# Cosmic_Pi_Main_Board_V2_5_OHL_no_logo.net
KiCad netlist of a schematic drawn in EAGLE
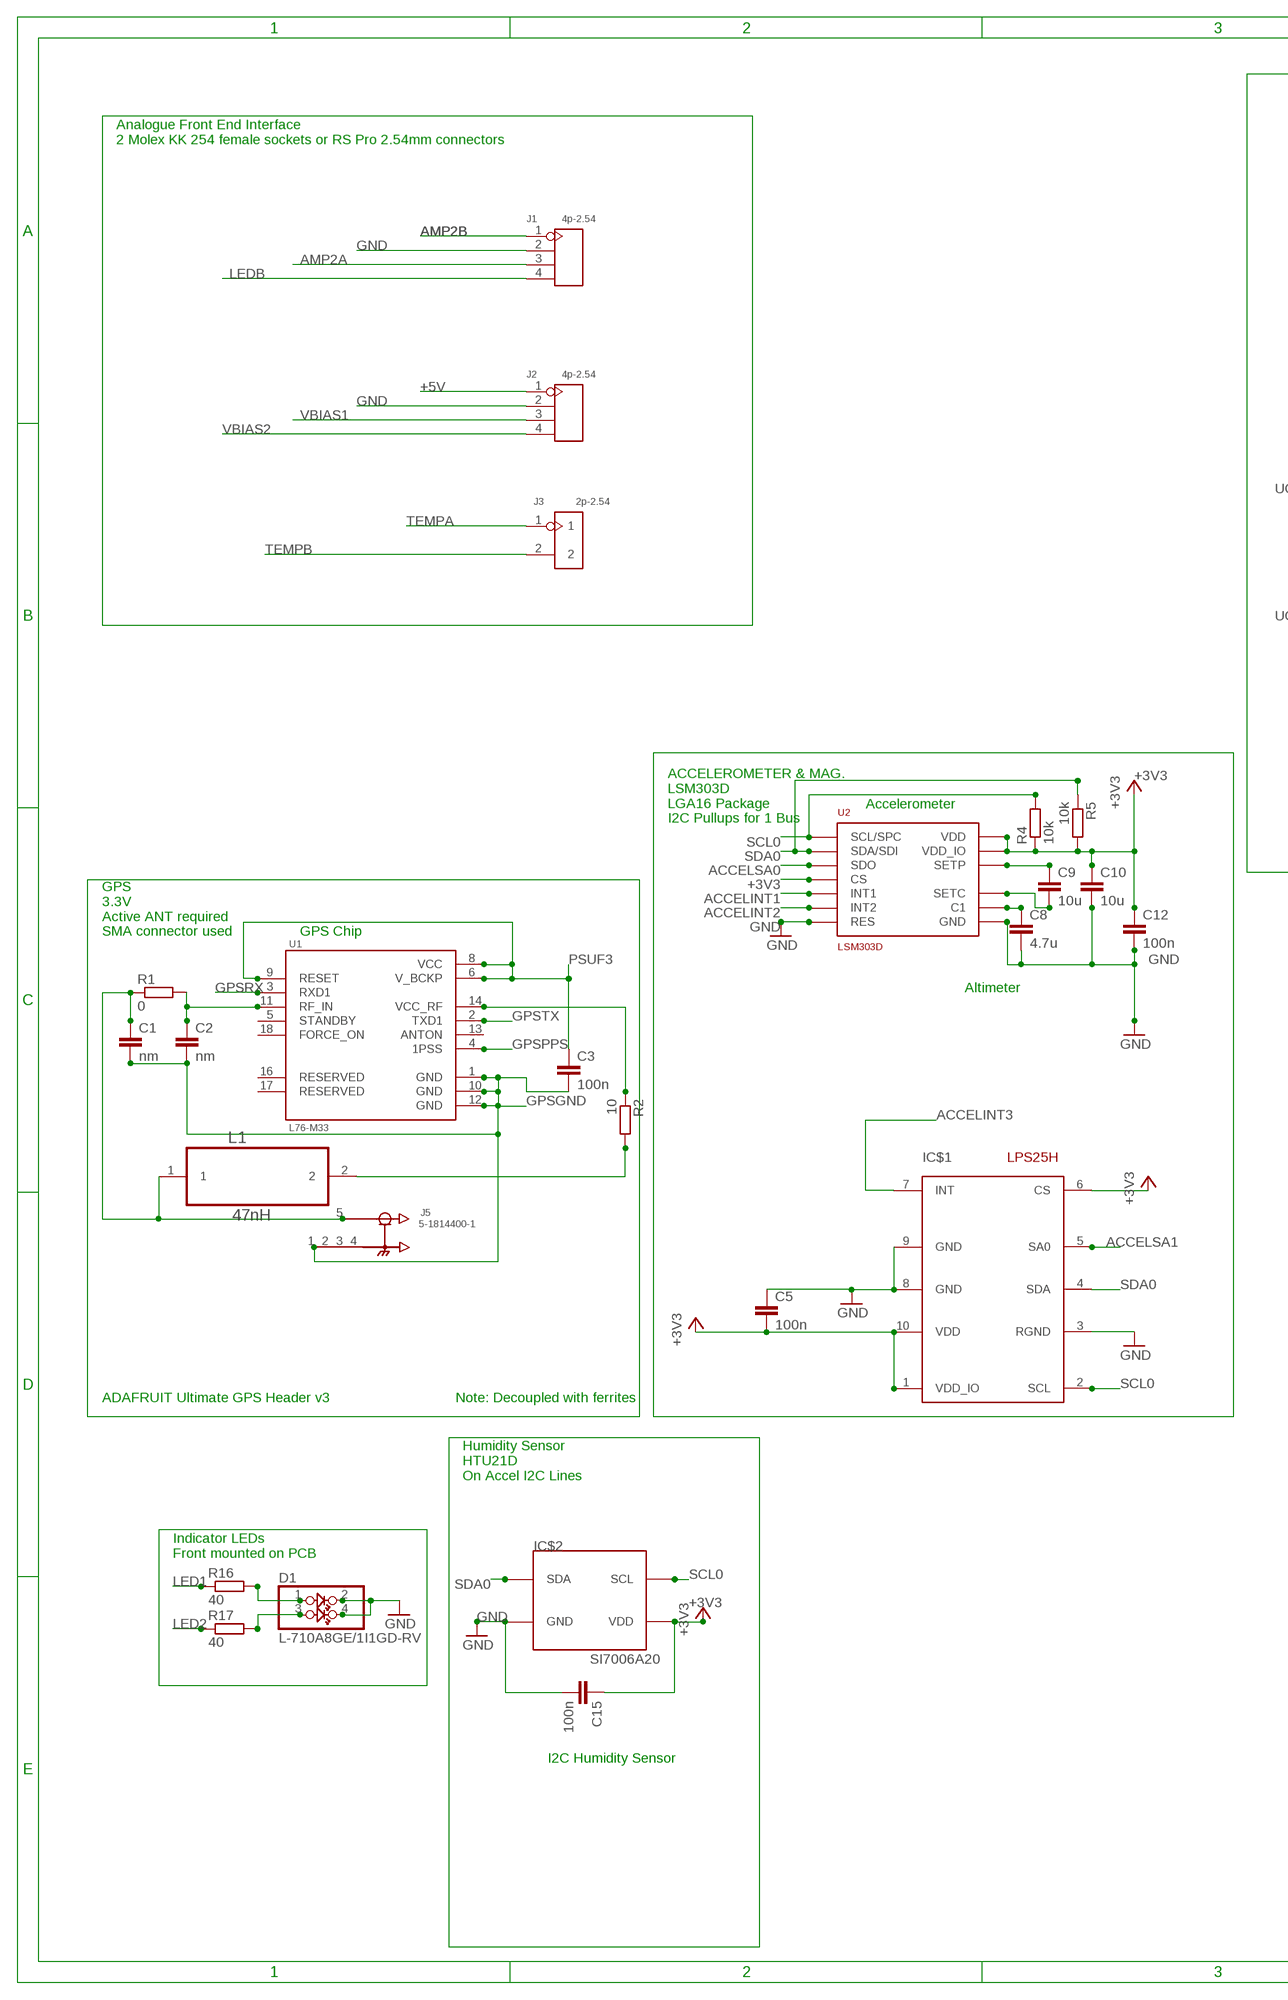
[diagram p0: schematic, sheet 1, part 1 of 2]
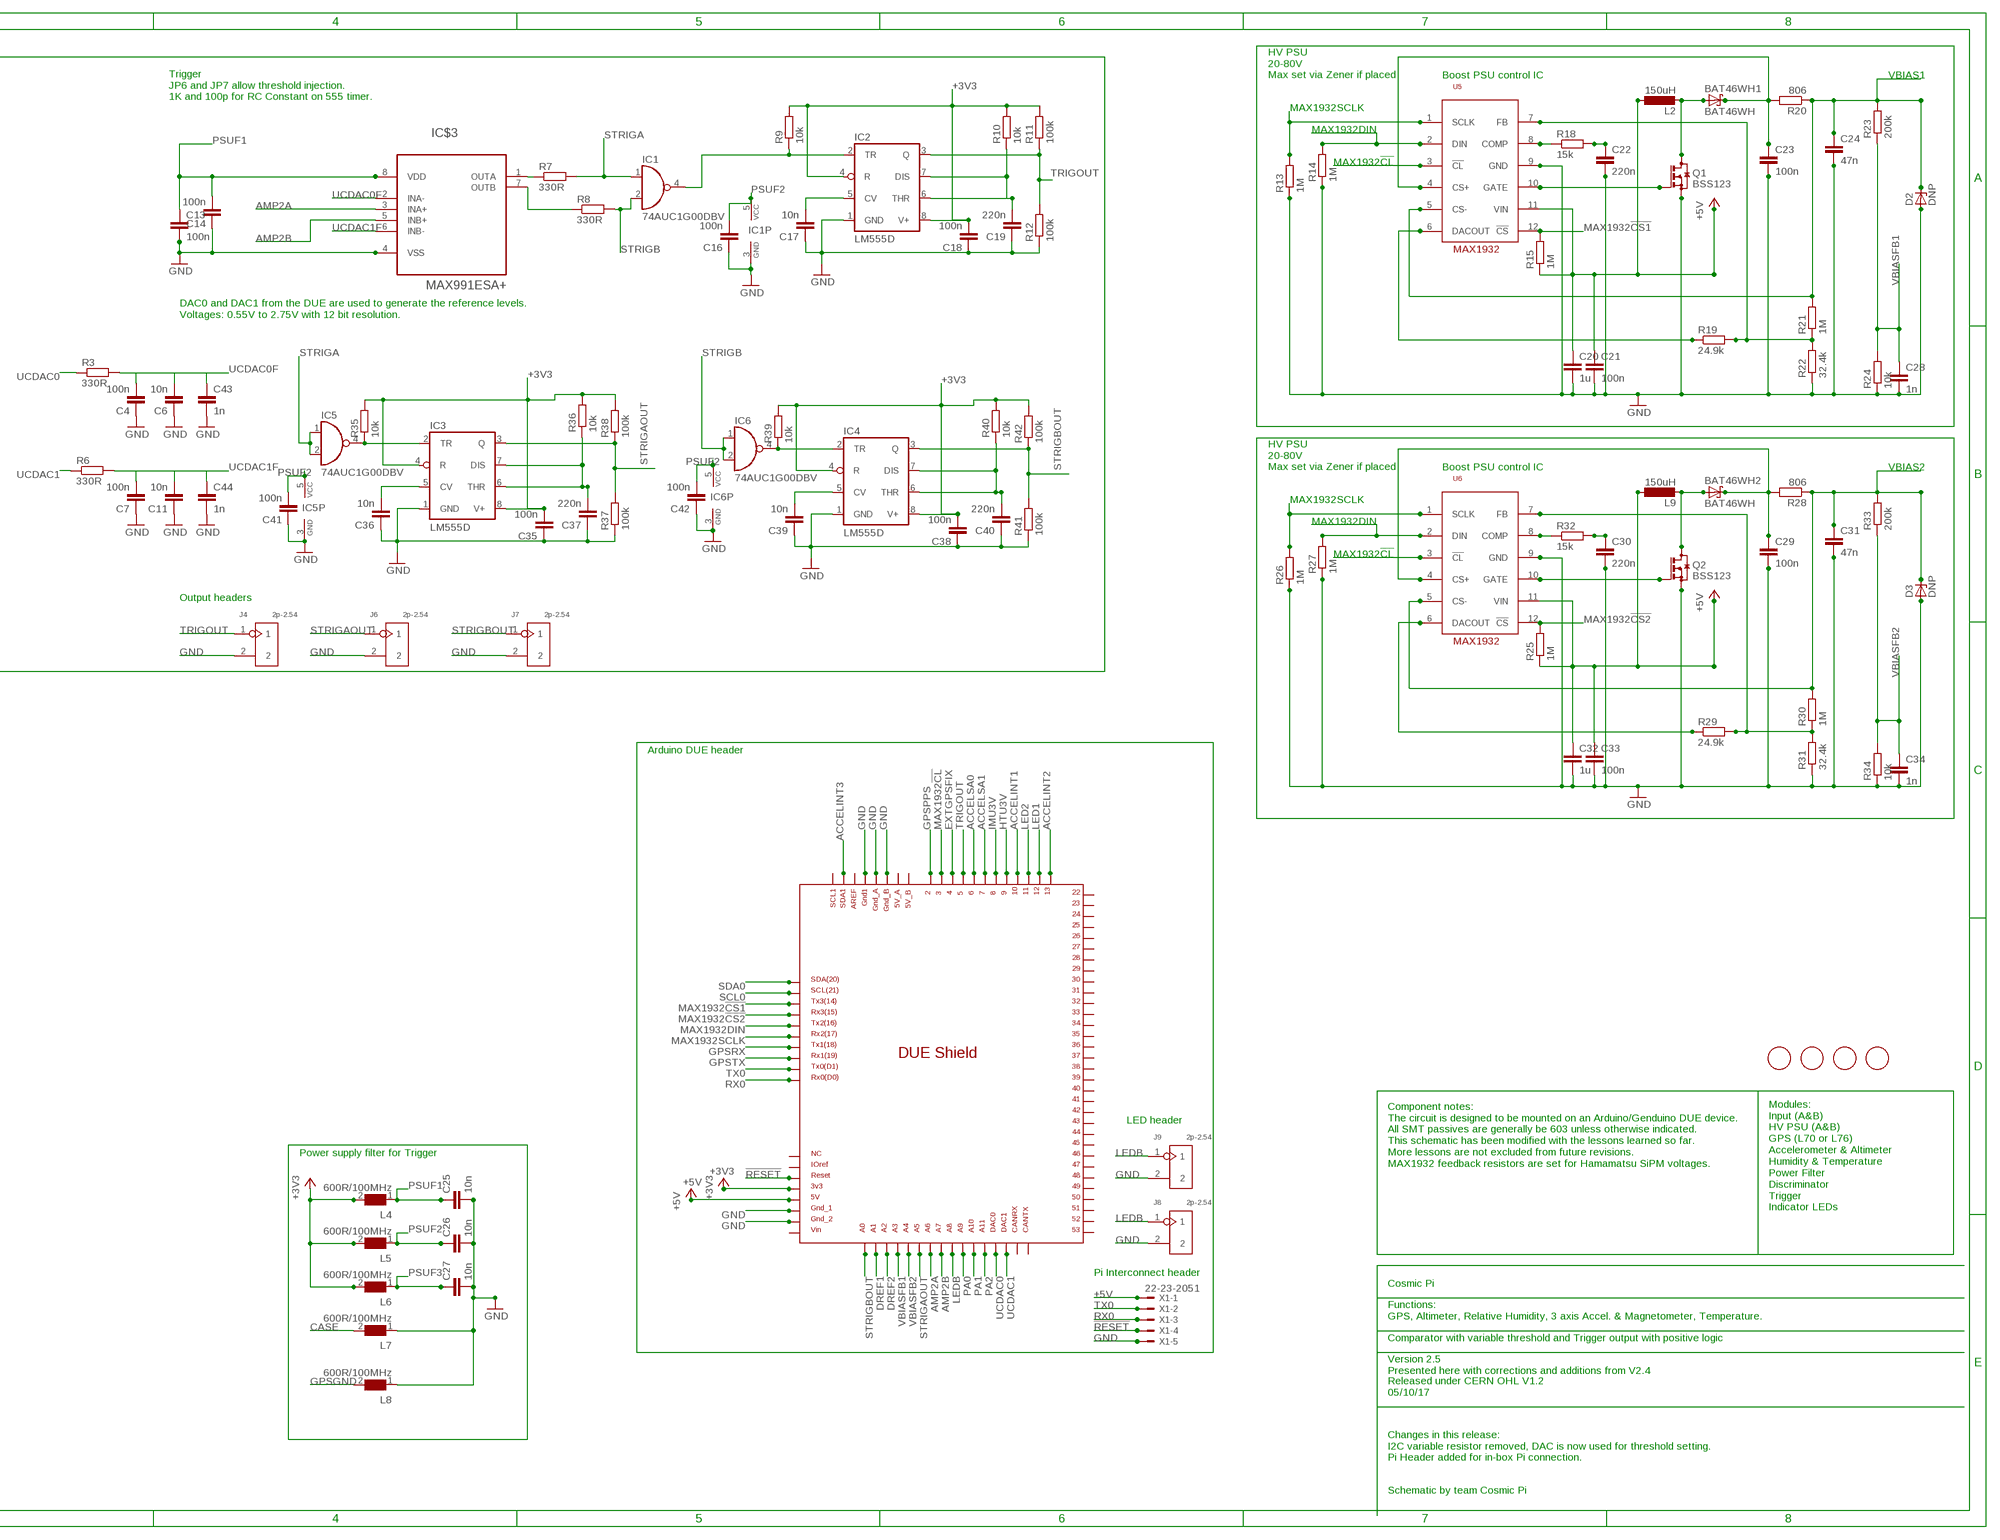
[diagram p1: schematic, sheet 1, part 2 of 2]

(export (version "E")
  (design (tool "Eeschema 10.0.6"))
  (components
    (comp (ref "BAT46WH1")
      (value "BAT46WH")
      (footprint "eagle-import:SOD123F")
      (libsource (lib "eagle-import") (part "BAT46WH"))
    )
    (comp (ref "BAT46WH2")
      (value "BAT46WH")
      (footprint "eagle-import:SOD123F")
      (libsource (lib "eagle-import") (part "BAT46WH"))
    )
    (comp (ref "C1")
      (value "nm")
      (footprint "eagle-import:C0603")
      (libsource (lib "eagle-import") (part "resistor_348_C-EUC0603"))
    )
    (comp (ref "C2")
      (value "nm")
      (footprint "eagle-import:C0603")
      (libsource (lib "eagle-import") (part "resistor_348_C-EUC0603"))
    )
    (comp (ref "C3")
      (value "100n")
      (footprint "eagle-import:C0603")
      (libsource (lib "eagle-import") (part "resistor_348_C-EUC0603"))
    )
    (comp (ref "C4")
      (value "100n")
      (footprint "eagle-import:C0603")
      (libsource (lib "eagle-import") (part "resistor_348_C-EUC0603"))
    )
    (comp (ref "C5")
      (value "100n")
      (footprint "eagle-import:C0603")
      (libsource (lib "eagle-import") (part "resistor_348_C-EUC0603"))
    )
    (comp (ref "C6")
      (value "10n")
      (footprint "eagle-import:C0603")
      (libsource (lib "eagle-import") (part "resistor_348_C-EUC0603"))
    )
    (comp (ref "C7")
      (value "100n")
      (footprint "eagle-import:C0603")
      (libsource (lib "eagle-import") (part "resistor_348_C-EUC0603"))
    )
    (comp (ref "C8")
      (value "4.7u")
      (footprint "eagle-import:C0603")
      (libsource (lib "eagle-import") (part "resistor_348_C-EUC0603"))
    )
    (comp (ref "C9")
      (value "10u")
      (footprint "eagle-import:C0603")
      (libsource (lib "eagle-import") (part "resistor_348_C-EUC0603"))
    )
    (comp (ref "C10")
      (value "10u")
      (footprint "eagle-import:C0603")
      (libsource (lib "eagle-import") (part "resistor_348_C-EUC0603"))
    )
    (comp (ref "C11")
      (value "10n")
      (footprint "eagle-import:C0603")
      (libsource (lib "eagle-import") (part "resistor_348_C-EUC0603"))
    )
    (comp (ref "C12")
      (value "100n")
      (footprint "eagle-import:C0603")
      (libsource (lib "eagle-import") (part "resistor_348_C-EUC0603"))
    )
    (comp (ref "C13")
      (value "100n")
      (footprint "eagle-import:C0603")
      (libsource (lib "eagle-import") (part "resistor_348_C-EUC0603"))
    )
    (comp (ref "C14")
      (value "100n")
      (footprint "eagle-import:C0603")
      (libsource (lib "eagle-import") (part "resistor_348_C-EUC0603"))
    )
    (comp (ref "C15")
      (value "100n")
      (footprint "eagle-import:C0603")
      (libsource (lib "eagle-import") (part "resistor_348_C-EUC0603"))
    )
    (comp (ref "C16")
      (value "100n")
      (footprint "eagle-import:C0603")
      (libsource (lib "eagle-import") (part "resistor_348_C-EUC0603"))
    )
    (comp (ref "C17")
      (value "10n")
      (footprint "eagle-import:C0603")
      (libsource (lib "eagle-import") (part "resistor_348_C-EUC0603"))
    )
    (comp (ref "C18")
      (value "100n")
      (footprint "eagle-import:C0603")
      (libsource (lib "eagle-import") (part "resistor_348_C-EUC0603"))
    )
    (comp (ref "C19")
      (value "220n")
      (footprint "eagle-import:C0603")
      (libsource (lib "eagle-import") (part "resistor_348_C-EUC0603"))
    )
    (comp (ref "C20")
      (value "1u")
      (footprint "eagle-import:C0603")
      (libsource (lib "eagle-import") (part "resistor_348_C-EUC0603"))
    )
    (comp (ref "C21")
      (value "100n")
      (footprint "eagle-import:C0603")
      (libsource (lib "eagle-import") (part "resistor_348_C-EUC0603"))
    )
    (comp (ref "C22")
      (value "220n")
      (footprint "eagle-import:C0603")
      (libsource (lib "eagle-import") (part "C-EUC0603"))
    )
    (comp (ref "C23")
      (value "100n")
      (footprint "eagle-import:C0603")
      (libsource (lib "eagle-import") (part "C-EUC0603"))
    )
    (comp (ref "C24")
      (value "47n")
      (footprint "eagle-import:C0603")
      (libsource (lib "eagle-import") (part "C-EUC0603"))
    )
    (comp (ref "C25")
      (value "10n")
      (footprint "eagle-import:C0603")
      (libsource (lib "eagle-import") (part "resistor_348_C-EUC0603"))
    )
    (comp (ref "C26")
      (value "10n")
      (footprint "eagle-import:C0603")
      (libsource (lib "eagle-import") (part "resistor_348_C-EUC0603"))
    )
    (comp (ref "C27")
      (value "10n")
      (footprint "eagle-import:C0603")
      (libsource (lib "eagle-import") (part "resistor_348_C-EUC0603"))
    )
    (comp (ref "C28")
      (value "1n")
      (footprint "eagle-import:C0603")
      (libsource (lib "eagle-import") (part "C-EUC0603"))
    )
    (comp (ref "C29")
      (value "100n")
      (footprint "eagle-import:C0603")
      (libsource (lib "eagle-import") (part "C-EUC0603"))
    )
    (comp (ref "C30")
      (value "220n")
      (footprint "eagle-import:C0603")
      (libsource (lib "eagle-import") (part "C-EUC0603"))
    )
    (comp (ref "C31")
      (value "47n")
      (footprint "eagle-import:C0603")
      (libsource (lib "eagle-import") (part "C-EUC0603"))
    )
    (comp (ref "C32")
      (value "1u")
      (footprint "eagle-import:C0603")
      (libsource (lib "eagle-import") (part "resistor_348_C-EUC0603"))
    )
    (comp (ref "C33")
      (value "100n")
      (footprint "eagle-import:C0603")
      (libsource (lib "eagle-import") (part "resistor_348_C-EUC0603"))
    )
    (comp (ref "C34")
      (value "1n")
      (footprint "eagle-import:C0603")
      (libsource (lib "eagle-import") (part "C-EUC0603"))
    )
    (comp (ref "C35")
      (value "100n")
      (footprint "eagle-import:C0603")
      (libsource (lib "eagle-import") (part "resistor_348_C-EUC0603"))
    )
    (comp (ref "C36")
      (value "10n")
      (footprint "eagle-import:C0603")
      (libsource (lib "eagle-import") (part "resistor_348_C-EUC0603"))
    )
    (comp (ref "C37")
      (value "220n")
      (footprint "eagle-import:C0603")
      (libsource (lib "eagle-import") (part "resistor_348_C-EUC0603"))
    )
    (comp (ref "C38")
      (value "100n")
      (footprint "eagle-import:C0603")
      (libsource (lib "eagle-import") (part "resistor_348_C-EUC0603"))
    )
    (comp (ref "C39")
      (value "10n")
      (footprint "eagle-import:C0603")
      (libsource (lib "eagle-import") (part "resistor_348_C-EUC0603"))
    )
    (comp (ref "C40")
      (value "220n")
      (footprint "eagle-import:C0603")
      (libsource (lib "eagle-import") (part "resistor_348_C-EUC0603"))
    )
    (comp (ref "C41")
      (value "100n")
      (footprint "eagle-import:C0603")
      (libsource (lib "eagle-import") (part "resistor_348_C-EUC0603"))
    )
    (comp (ref "C42")
      (value "100n")
      (footprint "eagle-import:C0603")
      (libsource (lib "eagle-import") (part "resistor_348_C-EUC0603"))
    )
    (comp (ref "C43")
      (value "1n")
      (footprint "eagle-import:C0603")
      (libsource (lib "eagle-import") (part "C-EUC0603"))
    )
    (comp (ref "C44")
      (value "1n")
      (footprint "eagle-import:C0603")
      (libsource (lib "eagle-import") (part "C-EUC0603"))
    )
    (comp (ref "D1")
      (value "L-710A8GE/1I1GD-RV")
      (footprint "eagle-import:2X02")
      (libsource (lib "eagle-import") (part "KINGBRITET1"))
    )
    (comp (ref "D2")
      (value "DNP")
      (footprint "eagle-import:SOT23")
      (libsource (lib "eagle-import") (part "ZENER-DIODESOT23"))
    )
    (comp (ref "D3")
      (value "DNP")
      (footprint "eagle-import:SOT23")
      (libsource (lib "eagle-import") (part "ZENER-DIODESOT23"))
    )
    (comp (ref "DUE1")
      (value "DUE(NORMAL)")
      (footprint "eagle-import:DUE(NORMAL)")
      (libsource (lib "eagle-import") (part "DUE(NORMAL)"))
    )
    (comp (ref "IC$1")
      (value "LPS25H")
      (footprint "eagle-import:LPS25H")
      (libsource (lib "eagle-import") (part "LPS25H"))
    )
    (comp (ref "IC$2")
      (value "SI7006A20")
      (footprint "eagle-import:3X3DFN")
      (libsource (lib "eagle-import") (part "SI7006A20"))
    )
    (comp (ref "IC$3")
      (value "MAX991ESA+")
      (footprint "eagle-import:SOIC-8")
      (libsource (lib "eagle-import") (part "MAX991ESA+"))
    )
    (comp (ref "IC1")
      (value "74AUC1G00DBV")
      (footprint "eagle-import:SOT23-5")
      (libsource (lib "eagle-import") (part "741G00DBVAUC"))
    )
    (comp (ref "IC2")
      (value "LM555D")
      (footprint "eagle-import:SO08")
      (libsource (lib "eagle-import") (part "555DLM"))
    )
    (comp (ref "IC3")
      (value "LM555D")
      (footprint "eagle-import:SO08")
      (libsource (lib "eagle-import") (part "555DLM"))
    )
    (comp (ref "IC4")
      (value "LM555D")
      (footprint "eagle-import:SO08")
      (libsource (lib "eagle-import") (part "555DLM"))
    )
    (comp (ref "IC5")
      (value "74AUC1G00DBV")
      (footprint "eagle-import:SOT23-5")
      (libsource (lib "eagle-import") (part "741G00DBVAUC"))
    )
    (comp (ref "IC6")
      (value "74AUC1G00DBV")
      (footprint "eagle-import:SOT23-5")
      (libsource (lib "eagle-import") (part "741G00DBVAUC"))
    )
    (comp (ref "J1")
      (value "4p-2.54")
      (footprint "eagle-import:H4-2.54")
      (fields (field (name "MPN") "F185-1104A1BSYA1"))
      (libsource (lib "eagle-import") (part "DIP-BLACK-FEMALE-HEADER-VERT(4P-2.54)"))
    )
    (comp (ref "J2")
      (value "4p-2.54")
      (footprint "eagle-import:H4-2.54")
      (fields (field (name "MPN") "F185-1104A1BSYA1"))
      (libsource (lib "eagle-import") (part "DIP-BLACK-FEMALE-HEADER-VERT(4P-2.54)"))
    )
    (comp (ref "J3")
      (value "2p-2.54")
      (footprint "eagle-import:H2-2.54")
      (fields (field (name "MPN") "P125-1102A0BS116A1"))
      (libsource (lib "eagle-import") (part "DIP-BLACK-MALE-HEADER-VERT(2P-2.54)"))
    )
    (comp (ref "J4")
      (value "2p-2.54")
      (footprint "eagle-import:H2-2.54")
      (fields (field (name "MPN") "P125-1102A0BS116A1"))
      (libsource (lib "eagle-import") (part "DIP-BLACK-MALE-HEADER-VERT(2P-2.54)"))
    )
    (comp (ref "J5")
      (value "5-1814400-1")
      (footprint "eagle-import:TE_5-1814400-1")
      (libsource (lib "eagle-import") (part "5-1814400-1"))
    )
    (comp (ref "J6")
      (value "2p-2.54")
      (footprint "eagle-import:H2-2.54")
      (fields (field (name "MPN") "P125-1102A0BS116A1"))
      (libsource (lib "eagle-import") (part "DIP-BLACK-MALE-HEADER-VERT(2P-2.54)"))
    )
    (comp (ref "J7")
      (value "2p-2.54")
      (footprint "eagle-import:H2-2.54")
      (fields (field (name "MPN") "P125-1102A0BS116A1"))
      (libsource (lib "eagle-import") (part "DIP-BLACK-MALE-HEADER-VERT(2P-2.54)"))
    )
    (comp (ref "J8")
      (value "2p-2.54")
      (footprint "eagle-import:H2-2.54")
      (fields (field (name "MPN") "P125-1102A0BS116A1"))
      (libsource (lib "eagle-import") (part "DIP-BLACK-MALE-HEADER-VERT(2P-2.54)"))
    )
    (comp (ref "J9")
      (value "2p-2.54")
      (footprint "eagle-import:H2-2.54")
      (fields (field (name "MPN") "P125-1102A0BS116A1"))
      (libsource (lib "eagle-import") (part "DIP-BLACK-MALE-HEADER-VERT(2P-2.54)"))
    )
    (comp (ref "L1")
      (value "47nH")
      (footprint "eagle-import:INDC1608X90N")
      (libsource (lib "eagle-import") (part "B82496C3470J"))
    )
    (comp (ref "L2")
      (value "150uH")
      (footprint "eagle-import:L1812")
      (libsource (lib "eagle-import") (part "L-EUL1812"))
    )
    (comp (ref "L4")
      (value "600R/100MHz")
      (footprint "eagle-import:1206")
      (fields (field (name "MPN") "74279218"))
      (libsource (lib "eagle-import") (part "WE-CBF_1206-74279218"))
    )
    (comp (ref "L5")
      (value "600R/100MHz")
      (footprint "eagle-import:1206")
      (fields (field (name "MPN") "74279218"))
      (libsource (lib "eagle-import") (part "WE-CBF_1206-74279218"))
    )
    (comp (ref "L6")
      (value "600R/100MHz")
      (footprint "eagle-import:1206")
      (fields (field (name "MPN") "74279218"))
      (libsource (lib "eagle-import") (part "WE-CBF_1206-74279218"))
    )
    (comp (ref "L7")
      (value "600R/100MHz")
      (footprint "eagle-import:1206")
      (fields (field (name "MPN") "74279218"))
      (libsource (lib "eagle-import") (part "WE-CBF_1206-74279218"))
    )
    (comp (ref "L8")
      (value "600R/100MHz")
      (footprint "eagle-import:1206")
      (fields (field (name "MPN") "74279218"))
      (libsource (lib "eagle-import") (part "WE-CBF_1206-74279218"))
    )
    (comp (ref "L9")
      (value "150uH")
      (footprint "eagle-import:L1812")
      (libsource (lib "eagle-import") (part "L-EUL1812"))
    )
    (comp (ref "Q1")
      (value "BSS123")
      (footprint "eagle-import:SOT23")
      (libsource (lib "eagle-import") (part "BSS123"))
    )
    (comp (ref "Q2")
      (value "BSS123")
      (footprint "eagle-import:SOT23")
      (libsource (lib "eagle-import") (part "BSS123"))
    )
    (comp (ref "R1")
      (value "0")
      (footprint "eagle-import:R0603")
      (libsource (lib "eagle-import") (part "R-EU_R0603"))
    )
    (comp (ref "R2")
      (value "10")
      (footprint "eagle-import:R0603")
      (libsource (lib "eagle-import") (part "R-EU_R0603"))
    )
    (comp (ref "R3")
      (value "330R")
      (footprint "eagle-import:R0603")
      (libsource (lib "eagle-import") (part "R-EU_R0603"))
    )
    (comp (ref "R4")
      (value "10k")
      (footprint "eagle-import:R0603")
      (libsource (lib "eagle-import") (part "R-EU_R0603"))
    )
    (comp (ref "R5")
      (value "10k")
      (footprint "eagle-import:R0603")
      (libsource (lib "eagle-import") (part "R-EU_R0603"))
    )
    (comp (ref "R6")
      (value "330R")
      (footprint "eagle-import:R0603")
      (libsource (lib "eagle-import") (part "R-EU_R0603"))
    )
    (comp (ref "R7")
      (value "330R")
      (footprint "eagle-import:R0603")
      (libsource (lib "eagle-import") (part "R-EU_R0603"))
    )
    (comp (ref "R8")
      (value "330R")
      (footprint "eagle-import:R0603")
      (libsource (lib "eagle-import") (part "R-EU_R0603"))
    )
    (comp (ref "R9")
      (value "10k")
      (footprint "eagle-import:R0603")
      (libsource (lib "eagle-import") (part "R-EU_R0603"))
    )
    (comp (ref "R10")
      (value "10k")
      (footprint "eagle-import:R0603")
      (libsource (lib "eagle-import") (part "R-EU_R0603"))
    )
    (comp (ref "R11")
      (value "100k")
      (footprint "eagle-import:R0603")
      (libsource (lib "eagle-import") (part "R-EU_R0603"))
    )
    (comp (ref "R12")
      (value "100k")
      (footprint "eagle-import:R0603")
      (libsource (lib "eagle-import") (part "R-EU_R0603"))
    )
    (comp (ref "R13")
      (value "1M")
      (footprint "eagle-import:R0603")
      (libsource (lib "eagle-import") (part "R-EU_R0603"))
    )
    (comp (ref "R14")
      (value "1M")
      (footprint "eagle-import:R0603")
      (libsource (lib "eagle-import") (part "R-EU_R0603"))
    )
    (comp (ref "R15")
      (value "1M")
      (footprint "eagle-import:R0603")
      (libsource (lib "eagle-import") (part "R-EU_R0603"))
    )
    (comp (ref "R16")
      (value "40")
      (footprint "eagle-import:R0603")
      (libsource (lib "eagle-import") (part "R-EU_R0603"))
    )
    (comp (ref "R17")
      (value "40")
      (footprint "eagle-import:R0603")
      (libsource (lib "eagle-import") (part "R-EU_R0603"))
    )
    (comp (ref "R18")
      (value "15k")
      (footprint "eagle-import:R0603")
      (libsource (lib "eagle-import") (part "R-EU_R0603"))
    )
    (comp (ref "R19")
      (value "24.9k")
      (footprint "eagle-import:R0603")
      (libsource (lib "eagle-import") (part "R-EU_R0603"))
    )
    (comp (ref "R20")
      (value "806")
      (footprint "eagle-import:R0603")
      (libsource (lib "eagle-import") (part "R-EU_R0603"))
    )
    (comp (ref "R21")
      (value "1M")
      (footprint "eagle-import:R0603")
      (libsource (lib "eagle-import") (part "R-EU_R0603"))
    )
    (comp (ref "R22")
      (value "32.4k")
      (footprint "eagle-import:R0603")
      (libsource (lib "eagle-import") (part "R-EU_R0603"))
    )
    (comp (ref "R23")
      (value "200k")
      (footprint "eagle-import:R0603")
      (libsource (lib "eagle-import") (part "R-EU_R0603"))
    )
    (comp (ref "R24")
      (value "10k")
      (footprint "eagle-import:R0603")
      (libsource (lib "eagle-import") (part "R-EU_R0603"))
    )
    (comp (ref "R25")
      (value "1M")
      (footprint "eagle-import:R0603")
      (libsource (lib "eagle-import") (part "R-EU_R0603"))
    )
    (comp (ref "R26")
      (value "1M")
      (footprint "eagle-import:R0603")
      (libsource (lib "eagle-import") (part "R-EU_R0603"))
    )
    (comp (ref "R27")
      (value "1M")
      (footprint "eagle-import:R0603")
      (libsource (lib "eagle-import") (part "R-EU_R0603"))
    )
    (comp (ref "R28")
      (value "806")
      (footprint "eagle-import:R0603")
      (libsource (lib "eagle-import") (part "R-EU_R0603"))
    )
    (comp (ref "R29")
      (value "24.9k")
      (footprint "eagle-import:R0603")
      (libsource (lib "eagle-import") (part "R-EU_R0603"))
    )
    (comp (ref "R30")
      (value "1M")
      (footprint "eagle-import:R0603")
      (libsource (lib "eagle-import") (part "R-EU_R0603"))
    )
    (comp (ref "R31")
      (value "32.4k")
      (footprint "eagle-import:R0603")
      (libsource (lib "eagle-import") (part "R-EU_R0603"))
    )
    (comp (ref "R32")
      (value "15k")
      (footprint "eagle-import:R0603")
      (libsource (lib "eagle-import") (part "R-EU_R0603"))
    )
    (comp (ref "R33")
      (value "200k")
      (footprint "eagle-import:R0603")
      (libsource (lib "eagle-import") (part "R-EU_R0603"))
    )
    (comp (ref "R34")
      (value "10k")
      (footprint "eagle-import:R0603")
      (libsource (lib "eagle-import") (part "R-EU_R0603"))
    )
    (comp (ref "R35")
      (value "10k")
      (footprint "eagle-import:R0603")
      (libsource (lib "eagle-import") (part "R-EU_R0603"))
    )
    (comp (ref "R36")
      (value "10k")
      (footprint "eagle-import:R0603")
      (libsource (lib "eagle-import") (part "R-EU_R0603"))
    )
    (comp (ref "R37")
      (value "100k")
      (footprint "eagle-import:R0603")
      (libsource (lib "eagle-import") (part "R-EU_R0603"))
    )
    (comp (ref "R38")
      (value "100k")
      (footprint "eagle-import:R0603")
      (libsource (lib "eagle-import") (part "R-EU_R0603"))
    )
    (comp (ref "R39")
      (value "10k")
      (footprint "eagle-import:R0603")
      (libsource (lib "eagle-import") (part "R-EU_R0603"))
    )
    (comp (ref "R40")
      (value "10k")
      (footprint "eagle-import:R0603")
      (libsource (lib "eagle-import") (part "R-EU_R0603"))
    )
    (comp (ref "R41")
      (value "100k")
      (footprint "eagle-import:R0603")
      (libsource (lib "eagle-import") (part "R-EU_R0603"))
    )
    (comp (ref "R42")
      (value "100k")
      (footprint "eagle-import:R0603")
      (libsource (lib "eagle-import") (part "R-EU_R0603"))
    )
    (comp (ref "U$1")
      (value "FIDUCIAL")
      (footprint "eagle-import:FIDUCIAL_1MM")
      (libsource (lib "eagle-import") (part "FIDUCIAL"))
    )
    (comp (ref "U$2")
      (value "FIDUCIAL")
      (footprint "eagle-import:FIDUCIAL_1MM")
      (libsource (lib "eagle-import") (part "FIDUCIAL"))
    )
    (comp (ref "U$3")
      (value "FIDUCIAL")
      (footprint "eagle-import:FIDUCIAL_1MM")
      (libsource (lib "eagle-import") (part "FIDUCIAL"))
    )
    (comp (ref "U$4")
      (value "FIDUCIAL")
      (footprint "eagle-import:FIDUCIAL_1MM")
      (libsource (lib "eagle-import") (part "FIDUCIAL"))
    )
    (comp (ref "U1")
      (value "L76-M33")
      (footprint "eagle-import:CAPCAV110P970X1010X250-18N")
      (libsource (lib "eagle-import") (part "L76-M33"))
    )
    (comp (ref "U2")
      (value "LSM303D")
      (footprint "eagle-import:LGA16L")
      (libsource (lib "eagle-import") (part "LSM303D"))
    )
    (comp (ref "U5")
      (value "MAX1932")
      (footprint "eagle-import:TQFN-12")
      (libsource (lib "eagle-import") (part "MAX1932"))
    )
    (comp (ref "U6")
      (value "MAX1932")
      (footprint "eagle-import:TQFN-12")
      (libsource (lib "eagle-import") (part "MAX1932"))
    )
    (comp (ref "X1")
      (value "22-23-2051")
      (footprint "eagle-import:22-23-2051")
      (fields (field (name "MF") "MOLEX"))
      (libsource (lib "eagle-import") (part "22-23-2051"))
    )
  )
  (nets
    (net (code "1") (name "+3V3") (class "Default")
      (node (ref "C10") (pin "1") (pinfunction "1_1") (pintype "passive"))
      (node (ref "C12") (pin "1") (pinfunction "1_1") (pintype "passive"))
      (node (ref "C15") (pin "1") (pinfunction "1_1") (pintype "passive"))
      (node (ref "C18") (pin "2") (pinfunction "2_2") (pintype "passive"))
      (node (ref "C35") (pin "2") (pinfunction "2_2") (pintype "passive"))
      (node (ref "C38") (pin "2") (pinfunction "2_2") (pintype "passive"))
      (node (ref "C5") (pin "2") (pinfunction "2_2") (pintype "passive"))
      (node (ref "DUE1") (pin "3V3") (pinfunction "3V3_3V3") (pintype "bidirectional"))
      (node (ref "IC$1") (pin "1") (pinfunction "VDD_IO_1") (pintype "power_in"))
      (node (ref "IC$1") (pin "10") (pinfunction "VDD_10") (pintype "power_in"))
      (node (ref "IC$1") (pin "6") (pinfunction "CS_6") (pintype "bidirectional"))
      (node (ref "IC$2") (pin "P$5") (pinfunction "VDD_P$5") (pintype "bidirectional"))
      (node (ref "IC2") (pin "4") (pinfunction "R_4") (pintype "input"))
      (node (ref "IC2") (pin "8") (pinfunction "V+_8") (pintype "power_in"))
      (node (ref "IC3") (pin "4") (pinfunction "R_4") (pintype "input"))
      (node (ref "IC3") (pin "8") (pinfunction "V+_8") (pintype "power_in"))
      (node (ref "IC4") (pin "4") (pinfunction "R_4") (pintype "input"))
      (node (ref "IC4") (pin "8") (pinfunction "V+_8") (pintype "power_in"))
      (node (ref "L4") (pin "2") (pinfunction "2_2") (pintype "passive"))
      (node (ref "L5") (pin "2") (pinfunction "2_2") (pintype "passive"))
      (node (ref "L6") (pin "2") (pinfunction "2_2") (pintype "passive"))
      (node (ref "R10") (pin "2") (pinfunction "2_2") (pintype "passive"))
      (node (ref "R11") (pin "2") (pinfunction "2_2") (pintype "passive"))
      (node (ref "R35") (pin "2") (pinfunction "2_2") (pintype "passive"))
      (node (ref "R36") (pin "2") (pinfunction "2_2") (pintype "passive"))
      (node (ref "R38") (pin "2") (pinfunction "2_2") (pintype "passive"))
      (node (ref "R39") (pin "2") (pinfunction "2_2") (pintype "passive"))
      (node (ref "R4") (pin "1") (pinfunction "1_1") (pintype "passive"))
      (node (ref "R40") (pin "2") (pinfunction "2_2") (pintype "passive"))
      (node (ref "R42") (pin "2") (pinfunction "2_2") (pintype "passive"))
      (node (ref "R5") (pin "2") (pinfunction "2_2") (pintype "passive"))
      (node (ref "R9") (pin "2") (pinfunction "2_2") (pintype "passive"))
      (node (ref "U2") (pin "P$1") (pinfunction "VDD_IO_P$1") (pintype "power_in"))
      (node (ref "U2") (pin "P$14") (pinfunction "VDD_P$14") (pintype "power_in"))
      (node (ref "U2") (pin "P$8") (pinfunction "CS_P$8") (pintype "bidirectional"))
    )
    (net (code "2") (name "+5V") (class "Default")
      (node (ref "C20") (pin "1") (pinfunction "1_1") (pintype "passive"))
      (node (ref "C21") (pin "1") (pinfunction "1_1") (pintype "passive"))
      (node (ref "C32") (pin "1") (pinfunction "1_1") (pintype "passive"))
      (node (ref "C33") (pin "1") (pinfunction "1_1") (pintype "passive"))
      (node (ref "DUE1") (pin "5V") (pinfunction "5V_5V") (pintype "bidirectional"))
      (node (ref "J2") (pin "1") (pinfunction "P$1_1") (pintype "bidirectional"))
      (node (ref "L2") (pin "1") (pinfunction "1_1") (pintype "passive"))
      (node (ref "L9") (pin "1") (pinfunction "1_1") (pintype "passive"))
      (node (ref "R15") (pin "1") (pinfunction "1_1") (pintype "passive"))
      (node (ref "R25") (pin "1") (pinfunction "1_1") (pintype "passive"))
      (node (ref "U5") (pin "11") (pinfunction "VIN_11") (pintype "bidirectional"))
      (node (ref "U6") (pin "11") (pinfunction "VIN_11") (pintype "bidirectional"))
      (node (ref "X1") (pin "1") (pinfunction "S_1") (pintype "passive"))
    )
    (net (code "3") (name "/ACCELINT1") (class "Default")
      (node (ref "DUE1") (pin "10") (pinfunction "10_10") (pintype "bidirectional"))
      (node (ref "U2") (pin "P$11") (pinfunction "INT1_P$11") (pintype "bidirectional"))
    )
    (net (code "4") (name "/ACCELINT2") (class "Default")
      (node (ref "DUE1") (pin "13") (pinfunction "13_13") (pintype "bidirectional"))
      (node (ref "U2") (pin "P$9") (pinfunction "INT2_P$9") (pintype "bidirectional"))
    )
    (net (code "5") (name "/ACCELINT3") (class "Default")
      (node (ref "DUE1") (pin "SDA1") (pinfunction "SDA1_SDA1") (pintype "bidirectional"))
      (node (ref "IC$1") (pin "7") (pinfunction "INT_7") (pintype "bidirectional"))
    )
    (net (code "6") (name "/ACCELSA0") (class "Default")
      (node (ref "DUE1") (pin "6") (pinfunction "6_6") (pintype "bidirectional"))
      (node (ref "U2") (pin "P$7") (pinfunction "SDO_P$7") (pintype "bidirectional"))
    )
    (net (code "7") (name "/ACCELSA1") (class "Default")
      (node (ref "DUE1") (pin "7") (pinfunction "7_7") (pintype "bidirectional"))
      (node (ref "IC$1") (pin "5") (pinfunction "SA0_5") (pintype "bidirectional"))
    )
    (net (code "8") (name "/AMP2A") (class "Default")
      (node (ref "DUE1") (pin "A6") (pinfunction "A6_A6") (pintype "bidirectional"))
      (node (ref "IC$3") (pin "3") (pinfunction "INA+_3") (pintype "input"))
      (node (ref "J1") (pin "3") (pinfunction "P$3_3") (pintype "bidirectional"))
    )
    (net (code "9") (name "/AMP2B") (class "Default")
      (node (ref "DUE1") (pin "A7") (pinfunction "A7_A7") (pintype "bidirectional"))
      (node (ref "IC$3") (pin "5") (pinfunction "INB+_5") (pintype "input"))
      (node (ref "J1") (pin "1") (pinfunction "P$1_1") (pintype "bidirectional"))
    )
    (net (code "10") (name "/CASE") (class "Default")
      (node (ref "L7") (pin "2") (pinfunction "2_2") (pintype "passive"))
    )
    (net (code "11") (name "/DREF1") (class "Default")
      (node (ref "DUE1") (pin "A1") (pinfunction "A1_A1") (pintype "bidirectional"))
    )
    (net (code "12") (name "/DREF2") (class "Default")
      (node (ref "DUE1") (pin "A2") (pinfunction "A2_A2") (pintype "bidirectional"))
    )
    (net (code "13") (name "/EXTGPSFIX") (class "Default")
      (node (ref "DUE1") (pin "4") (pinfunction "4_4") (pintype "bidirectional"))
    )
    (net (code "14") (name "/GPSGND") (class "Default")
      (node (ref "C1") (pin "2") (pinfunction "2_2") (pintype "passive"))
      (node (ref "C2") (pin "2") (pinfunction "2_2") (pintype "passive"))
      (node (ref "C3") (pin "2") (pinfunction "2_2") (pintype "passive"))
      (node (ref "J5") (pin "1") (pinfunction "GND_1") (pintype "passive"))
      (node (ref "L8") (pin "2") (pinfunction "2_2") (pintype "passive"))
      (node (ref "U1") (pin "1") (pinfunction "GND_1") (pintype "power_in"))
      (node (ref "U1") (pin "10") (pinfunction "GND_10") (pintype "power_in"))
      (node (ref "U1") (pin "12") (pinfunction "GND_12") (pintype "power_in"))
    )
    (net (code "15") (name "/GPSPPS") (class "Default")
      (node (ref "DUE1") (pin "2") (pinfunction "2_2") (pintype "bidirectional"))
      (node (ref "U1") (pin "4") (pinfunction "1PSS_4") (pintype "output"))
    )
    (net (code "16") (name "/GPSRX") (class "Default")
      (node (ref "DUE1") (pin "TX1") (pinfunction "TX1_TX1") (pintype "bidirectional"))
      (node (ref "U1") (pin "3") (pinfunction "RXD1_3") (pintype "bidirectional"))
    )
    (net (code "17") (name "/GPSTX") (class "Default")
      (node (ref "DUE1") (pin "RX1") (pinfunction "RX1_RX1") (pintype "bidirectional"))
      (node (ref "U1") (pin "2") (pinfunction "TXD1_2") (pintype "output"))
    )
    (net (code "18") (name "/HTU3V") (class "Default")
      (node (ref "DUE1") (pin "9") (pinfunction "9_9") (pintype "bidirectional"))
    )
    (net (code "19") (name "/IMU3V") (class "Default")
      (node (ref "DUE1") (pin "8") (pinfunction "8_8") (pintype "bidirectional"))
    )
    (net (code "20") (name "/LED1") (class "Default")
      (node (ref "DUE1") (pin "12") (pinfunction "12_12") (pintype "bidirectional"))
      (node (ref "R16") (pin "1") (pinfunction "1_1") (pintype "passive"))
    )
    (net (code "21") (name "/LED2") (class "Default")
      (node (ref "DUE1") (pin "11") (pinfunction "11_11") (pintype "bidirectional"))
      (node (ref "R17") (pin "1") (pinfunction "1_1") (pintype "passive"))
    )
    (net (code "22") (name "/LEDB") (class "Default")
      (node (ref "DUE1") (pin "A8") (pinfunction "A8_A8") (pintype "bidirectional"))
      (node (ref "J1") (pin "4") (pinfunction "P$4_4") (pintype "bidirectional"))
      (node (ref "J8") (pin "1") (pinfunction "1_1") (pintype "bidirectional"))
      (node (ref "J9") (pin "1") (pinfunction "1_1") (pintype "bidirectional"))
    )
    (net (code "23") (name "/MAX1932DIN") (class "Default")
      (node (ref "DUE1") (pin "TX2") (pinfunction "TX2_TX2") (pintype "bidirectional"))
      (node (ref "R14") (pin "2") (pinfunction "2_2") (pintype "passive"))
      (node (ref "R27") (pin "2") (pinfunction "2_2") (pintype "passive"))
      (node (ref "U5") (pin "2") (pinfunction "DIN_2") (pintype "bidirectional"))
      (node (ref "U6") (pin "2") (pinfunction "DIN_2") (pintype "bidirectional"))
    )
    (net (code "24") (name "/MAX1932SCLK") (class "Default")
      (node (ref "DUE1") (pin "RX2") (pinfunction "RX2_RX2") (pintype "bidirectional"))
      (node (ref "R13") (pin "2") (pinfunction "2_2") (pintype "passive"))
      (node (ref "R26") (pin "2") (pinfunction "2_2") (pintype "passive"))
      (node (ref "U5") (pin "1") (pinfunction "SCLK_1") (pintype "bidirectional"))
      (node (ref "U6") (pin "1") (pinfunction "SCLK_1") (pintype "bidirectional"))
    )
    (net (code "25") (name "/MAX1932~{CL}") (class "Default")
      (node (ref "DUE1") (pin "3") (pinfunction "3_3") (pintype "bidirectional"))
      (node (ref "U5") (pin "3") (pinfunction "~{CL}_3") (pintype "bidirectional"))
      (node (ref "U6") (pin "3") (pinfunction "~{CL}_3") (pintype "bidirectional"))
    )
    (net (code "26") (name "/MAX1932~{CS1}") (class "Default")
      (node (ref "DUE1") (pin "TX3") (pinfunction "TX3_TX3") (pintype "bidirectional"))
      (node (ref "R15") (pin "2") (pinfunction "2_2") (pintype "passive"))
      (node (ref "U5") (pin "12") (pinfunction "~{CS}_12") (pintype "bidirectional"))
    )
    (net (code "27") (name "/MAX1932~{CS2}") (class "Default")
      (node (ref "DUE1") (pin "RX3") (pinfunction "RX3_RX3") (pintype "bidirectional"))
      (node (ref "R25") (pin "2") (pinfunction "2_2") (pintype "passive"))
      (node (ref "U6") (pin "12") (pinfunction "~{CS}_12") (pintype "bidirectional"))
    )
    (net (code "28") (name "/PA0") (class "Default")
      (node (ref "DUE1") (pin "A9") (pinfunction "A9_A9") (pintype "bidirectional"))
    )
    (net (code "29") (name "/PA1") (class "Default")
      (node (ref "DUE1") (pin "A10") (pinfunction "A10_A10") (pintype "bidirectional"))
    )
    (net (code "30") (name "/PA2") (class "Default")
      (node (ref "DUE1") (pin "A11") (pinfunction "A11_A11") (pintype "bidirectional"))
    )
    (net (code "31") (name "/PSUF1") (class "Default")
      (node (ref "C13") (pin "1") (pinfunction "1_1") (pintype "passive"))
      (node (ref "C14") (pin "2") (pinfunction "2_2") (pintype "passive"))
      (node (ref "C25") (pin "1") (pinfunction "1_1") (pintype "passive"))
      (node (ref "IC$3") (pin "8") (pinfunction "VDD_8") (pintype "power_in"))
      (node (ref "L4") (pin "1") (pinfunction "1_1") (pintype "passive"))
    )
    (net (code "32") (name "/PSUF2") (class "Default")
      (node (ref "C16") (pin "2") (pinfunction "2_2") (pintype "passive"))
      (node (ref "C26") (pin "1") (pinfunction "1_1") (pintype "passive"))
      (node (ref "C41") (pin "2") (pinfunction "2_2") (pintype "passive"))
      (node (ref "C42") (pin "2") (pinfunction "2_2") (pintype "passive"))
      (node (ref "IC1") (pin "5") (pinfunction "VCC_5") (pintype "power_in"))
      (node (ref "IC5") (pin "5") (pinfunction "VCC_5") (pintype "power_in"))
      (node (ref "IC6") (pin "5") (pinfunction "VCC_5") (pintype "power_in"))
      (node (ref "L5") (pin "1") (pinfunction "1_1") (pintype "passive"))
    )
    (net (code "33") (name "/PSUF3") (class "Default")
      (node (ref "C27") (pin "1") (pinfunction "1_1") (pintype "passive"))
      (node (ref "C3") (pin "1") (pinfunction "1_1") (pintype "passive"))
      (node (ref "L6") (pin "1") (pinfunction "1_1") (pintype "passive"))
      (node (ref "U1") (pin "6") (pinfunction "V_BCKP_6") (pintype "power_in"))
      (node (ref "U1") (pin "8") (pinfunction "VCC_8") (pintype "power_in"))
      (node (ref "U1") (pin "9") (pinfunction "RESET_9") (pintype "bidirectional"))
    )
    (net (code "34") (name "/RX0") (class "Default")
      (node (ref "DUE1") (pin "RX0") (pinfunction "RX0_RX0") (pintype "bidirectional"))
      (node (ref "X1") (pin "3") (pinfunction "S_3") (pintype "passive"))
    )
    (net (code "35") (name "/SCL0") (class "Default")
      (node (ref "DUE1") (pin "SCL") (pinfunction "SCL_SCL") (pintype "bidirectional"))
      (node (ref "IC$1") (pin "2") (pinfunction "SCL_2") (pintype "bidirectional"))
      (node (ref "IC$2") (pin "P$6") (pinfunction "SCL_P$6") (pintype "bidirectional"))
      (node (ref "R4") (pin "2") (pinfunction "2_2") (pintype "passive"))
      (node (ref "U2") (pin "P$4") (pinfunction "SCL/SPC_P$4") (pintype "bidirectional"))
    )
    (net (code "36") (name "/SDA0") (class "Default")
      (node (ref "DUE1") (pin "SDA") (pinfunction "SDA_SDA") (pintype "bidirectional"))
      (node (ref "IC$1") (pin "4") (pinfunction "SDA_4") (pintype "bidirectional"))
      (node (ref "IC$2") (pin "P$1") (pinfunction "SDA_P$1") (pintype "bidirectional"))
      (node (ref "R5") (pin "1") (pinfunction "1_1") (pintype "passive"))
      (node (ref "U2") (pin "P$6") (pinfunction "SDA/SDI_P$6") (pintype "bidirectional"))
    )
    (net (code "37") (name "/STRIGA") (class "Default")
      (node (ref "IC1") (pin "1") (pinfunction "I0_1") (pintype "input"))
      (node (ref "IC5") (pin "1") (pinfunction "I0_1") (pintype "input"))
      (node (ref "IC5") (pin "2") (pinfunction "I1_2") (pintype "input"))
      (node (ref "R7") (pin "2") (pinfunction "2_2") (pintype "passive"))
    )
    (net (code "38") (name "/STRIGAOUT") (class "Default")
      (node (ref "DUE1") (pin "A5") (pinfunction "A5_A5") (pintype "bidirectional"))
      (node (ref "IC3") (pin "3") (pinfunction "Q_3") (pintype "output"))
      (node (ref "J6") (pin "1") (pinfunction "1_1") (pintype "bidirectional"))
      (node (ref "R37") (pin "2") (pinfunction "2_2") (pintype "passive"))
      (node (ref "R38") (pin "1") (pinfunction "1_1") (pintype "passive"))
    )
    (net (code "39") (name "/STRIGB") (class "Default")
      (node (ref "IC1") (pin "2") (pinfunction "I1_2") (pintype "input"))
      (node (ref "IC6") (pin "1") (pinfunction "I0_1") (pintype "input"))
      (node (ref "IC6") (pin "2") (pinfunction "I1_2") (pintype "input"))
      (node (ref "R8") (pin "2") (pinfunction "2_2") (pintype "passive"))
    )
    (net (code "40") (name "/STRIGBOUT") (class "Default")
      (node (ref "DUE1") (pin "A0") (pinfunction "A0_A0") (pintype "bidirectional"))
      (node (ref "IC4") (pin "3") (pinfunction "Q_3") (pintype "output"))
      (node (ref "J7") (pin "1") (pinfunction "1_1") (pintype "bidirectional"))
      (node (ref "R41") (pin "2") (pinfunction "2_2") (pintype "passive"))
      (node (ref "R42") (pin "1") (pinfunction "1_1") (pintype "passive"))
    )
    (net (code "41") (name "/TEMPA") (class "Default")
      (node (ref "J3") (pin "1") (pinfunction "1_1") (pintype "bidirectional"))
    )
    (net (code "42") (name "/TEMPB") (class "Default")
      (node (ref "J3") (pin "2") (pinfunction "2_2") (pintype "bidirectional"))
    )
    (net (code "43") (name "/TRIGOUT") (class "Default")
      (node (ref "DUE1") (pin "5") (pinfunction "5_5") (pintype "bidirectional"))
      (node (ref "IC2") (pin "3") (pinfunction "Q_3") (pintype "output"))
      (node (ref "J4") (pin "1") (pinfunction "1_1") (pintype "bidirectional"))
      (node (ref "R11") (pin "1") (pinfunction "1_1") (pintype "passive"))
      (node (ref "R12") (pin "2") (pinfunction "2_2") (pintype "passive"))
    )
    (net (code "44") (name "/TX0") (class "Default")
      (node (ref "DUE1") (pin "TX0") (pinfunction "TX0_TX0") (pintype "bidirectional"))
      (node (ref "X1") (pin "2") (pinfunction "S_2") (pintype "passive"))
    )
    (net (code "45") (name "/UCDAC0") (class "Default")
      (node (ref "DUE1") (pin "DAC0") (pinfunction "DAC0_DAC0") (pintype "bidirectional"))
      (node (ref "R3") (pin "1") (pinfunction "1_1") (pintype "passive"))
    )
    (net (code "46") (name "/UCDAC0F") (class "Default")
      (node (ref "C4") (pin "2") (pinfunction "2_2") (pintype "passive"))
      (node (ref "C43") (pin "1") (pinfunction "1_1") (pintype "passive"))
      (node (ref "C6") (pin "2") (pinfunction "2_2") (pintype "passive"))
      (node (ref "IC$3") (pin "2") (pinfunction "INA-_2") (pintype "input"))
      (node (ref "R3") (pin "2") (pinfunction "2_2") (pintype "passive"))
    )
    (net (code "47") (name "/UCDAC1") (class "Default")
      (node (ref "DUE1") (pin "DAC1") (pinfunction "DAC1_DAC1") (pintype "bidirectional"))
      (node (ref "R6") (pin "1") (pinfunction "1_1") (pintype "passive"))
    )
    (net (code "48") (name "/UCDAC1F") (class "Default")
      (node (ref "C11") (pin "2") (pinfunction "2_2") (pintype "passive"))
      (node (ref "C44") (pin "1") (pinfunction "1_1") (pintype "passive"))
      (node (ref "C7") (pin "2") (pinfunction "2_2") (pintype "passive"))
      (node (ref "IC$3") (pin "6") (pinfunction "INB-_6") (pintype "input"))
      (node (ref "R6") (pin "2") (pinfunction "2_2") (pintype "passive"))
    )
    (net (code "49") (name "/VBIAS1") (class "Default")
      (node (ref "C24") (pin "1") (pinfunction "1_1") (pintype "passive"))
      (node (ref "D2") (pin "3") (pinfunction "C_3") (pintype "passive"))
      (node (ref "J2") (pin "3") (pinfunction "P$3_3") (pintype "bidirectional"))
      (node (ref "R20") (pin "1") (pinfunction "1_1") (pintype "passive"))
      (node (ref "R21") (pin "2") (pinfunction "2_2") (pintype "passive"))
      (node (ref "R23") (pin "2") (pinfunction "2_2") (pintype "passive"))
      (node (ref "U5") (pin "5") (pinfunction "CS-_5") (pintype "bidirectional"))
    )
    (net (code "50") (name "/VBIAS2") (class "Default")
      (node (ref "C31") (pin "1") (pinfunction "1_1") (pintype "passive"))
      (node (ref "D3") (pin "3") (pinfunction "C_3") (pintype "passive"))
      (node (ref "J2") (pin "4") (pinfunction "P$4_4") (pintype "bidirectional"))
      (node (ref "R28") (pin "1") (pinfunction "1_1") (pintype "passive"))
      (node (ref "R30") (pin "2") (pinfunction "2_2") (pintype "passive"))
      (node (ref "R33") (pin "2") (pinfunction "2_2") (pintype "passive"))
      (node (ref "U6") (pin "5") (pinfunction "CS-_5") (pintype "bidirectional"))
    )
    (net (code "51") (name "/VBIASFB1") (class "Default")
      (node (ref "C28") (pin "1") (pinfunction "1_1") (pintype "passive"))
      (node (ref "DUE1") (pin "A3") (pinfunction "A3_A3") (pintype "bidirectional"))
      (node (ref "R23") (pin "1") (pinfunction "1_1") (pintype "passive"))
      (node (ref "R24") (pin "2") (pinfunction "2_2") (pintype "passive"))
    )
    (net (code "52") (name "/VBIASFB2") (class "Default")
      (node (ref "C34") (pin "1") (pinfunction "1_1") (pintype "passive"))
      (node (ref "DUE1") (pin "A4") (pinfunction "A4_A4") (pintype "bidirectional"))
      (node (ref "R33") (pin "1") (pinfunction "1_1") (pintype "passive"))
      (node (ref "R34") (pin "2") (pinfunction "2_2") (pintype "passive"))
    )
    (net (code "53") (name "/~{RESET}") (class "Default")
      (node (ref "DUE1") (pin "RESET") (pinfunction "RESET_RESET") (pintype "bidirectional"))
      (node (ref "X1") (pin "4") (pinfunction "S_4") (pintype "passive"))
    )
    (net (code "54") (name "GND") (class "Default")
      (node (ref "C10") (pin "2") (pinfunction "2_2") (pintype "passive"))
      (node (ref "C11") (pin "1") (pinfunction "1_1") (pintype "passive"))
      (node (ref "C12") (pin "2") (pinfunction "2_2") (pintype "passive"))
      (node (ref "C13") (pin "2") (pinfunction "2_2") (pintype "passive"))
      (node (ref "C14") (pin "1") (pinfunction "1_1") (pintype "passive"))
      (node (ref "C15") (pin "2") (pinfunction "2_2") (pintype "passive"))
      (node (ref "C16") (pin "1") (pinfunction "1_1") (pintype "passive"))
      (node (ref "C17") (pin "1") (pinfunction "1_1") (pintype "passive"))
      (node (ref "C18") (pin "1") (pinfunction "1_1") (pintype "passive"))
      (node (ref "C19") (pin "1") (pinfunction "1_1") (pintype "passive"))
      (node (ref "C20") (pin "2") (pinfunction "2_2") (pintype "passive"))
      (node (ref "C21") (pin "2") (pinfunction "2_2") (pintype "passive"))
      (node (ref "C22") (pin "2") (pinfunction "2_2") (pintype "passive"))
      (node (ref "C23") (pin "2") (pinfunction "2_2") (pintype "passive"))
      (node (ref "C24") (pin "2") (pinfunction "2_2") (pintype "passive"))
      (node (ref "C25") (pin "2") (pinfunction "2_2") (pintype "passive"))
      (node (ref "C26") (pin "2") (pinfunction "2_2") (pintype "passive"))
      (node (ref "C27") (pin "2") (pinfunction "2_2") (pintype "passive"))
      (node (ref "C28") (pin "2") (pinfunction "2_2") (pintype "passive"))
      (node (ref "C29") (pin "2") (pinfunction "2_2") (pintype "passive"))
      (node (ref "C30") (pin "2") (pinfunction "2_2") (pintype "passive"))
      (node (ref "C31") (pin "2") (pinfunction "2_2") (pintype "passive"))
      (node (ref "C32") (pin "2") (pinfunction "2_2") (pintype "passive"))
      (node (ref "C33") (pin "2") (pinfunction "2_2") (pintype "passive"))
      (node (ref "C34") (pin "2") (pinfunction "2_2") (pintype "passive"))
      (node (ref "C35") (pin "1") (pinfunction "1_1") (pintype "passive"))
      (node (ref "C36") (pin "1") (pinfunction "1_1") (pintype "passive"))
      (node (ref "C37") (pin "1") (pinfunction "1_1") (pintype "passive"))
      (node (ref "C38") (pin "1") (pinfunction "1_1") (pintype "passive"))
      (node (ref "C39") (pin "1") (pinfunction "1_1") (pintype "passive"))
      (node (ref "C4") (pin "1") (pinfunction "1_1") (pintype "passive"))
      (node (ref "C40") (pin "1") (pinfunction "1_1") (pintype "passive"))
      (node (ref "C41") (pin "1") (pinfunction "1_1") (pintype "passive"))
      (node (ref "C42") (pin "1") (pinfunction "1_1") (pintype "passive"))
      (node (ref "C43") (pin "2") (pinfunction "2_2") (pintype "passive"))
      (node (ref "C44") (pin "2") (pinfunction "2_2") (pintype "passive"))
      (node (ref "C5") (pin "1") (pinfunction "1_1") (pintype "passive"))
      (node (ref "C6") (pin "1") (pinfunction "1_1") (pintype "passive"))
      (node (ref "C7") (pin "1") (pinfunction "1_1") (pintype "passive"))
      (node (ref "C8") (pin "2") (pinfunction "2_2") (pintype "passive"))
      (node (ref "D1") (pin "2") (pinfunction "2_2") (pintype "passive"))
      (node (ref "D1") (pin "4") (pinfunction "4_4") (pintype "passive"))
      (node (ref "D2") (pin "1") (pinfunction "A_1") (pintype "passive"))
      (node (ref "D3") (pin "1") (pinfunction "A_1") (pintype "passive"))
      (node (ref "DUE1") (pin "GND1") (pinfunction "GND1_GND1") (pintype "bidirectional"))
      (node (ref "DUE1") (pin "GND_1") (pinfunction "GND_1_GND_1") (pintype "bidirectional"))
      (node (ref "DUE1") (pin "GND_2") (pinfunction "GND_2_GND_2") (pintype "bidirectional"))
      (node (ref "DUE1") (pin "GND_A") (pinfunction "GND_A_GND_A") (pintype "bidirectional"))
      (node (ref "DUE1") (pin "GND_B") (pinfunction "GND_B_GND_B") (pintype "bidirectional"))
      (node (ref "IC$1") (pin "3") (pinfunction "RGND_3") (pintype "bidirectional"))
      (node (ref "IC$1") (pin "8") (pinfunction "GND_8") (pintype "power_in"))
      (node (ref "IC$1") (pin "9") (pinfunction "GND_9") (pintype "power_in"))
      (node (ref "IC$2") (pin "P$2") (pinfunction "GND_P$2") (pintype "bidirectional"))
      (node (ref "IC$3") (pin "4") (pinfunction "VSS_4") (pintype "power_in"))
      (node (ref "IC1") (pin "3") (pinfunction "GND_3") (pintype "power_in"))
      (node (ref "IC2") (pin "1") (pinfunction "GND_1") (pintype "power_in"))
      (node (ref "IC3") (pin "1") (pinfunction "GND_1") (pintype "power_in"))
      (node (ref "IC4") (pin "1") (pinfunction "GND_1") (pintype "power_in"))
      (node (ref "IC5") (pin "3") (pinfunction "GND_3") (pintype "power_in"))
      (node (ref "IC6") (pin "3") (pinfunction "GND_3") (pintype "power_in"))
      (node (ref "J1") (pin "2") (pinfunction "P$2_2") (pintype "bidirectional"))
      (node (ref "J2") (pin "2") (pinfunction "P$2_2") (pintype "bidirectional"))
      (node (ref "J4") (pin "2") (pinfunction "2_2") (pintype "bidirectional"))
      (node (ref "J6") (pin "2") (pinfunction "2_2") (pintype "bidirectional"))
      (node (ref "J7") (pin "2") (pinfunction "2_2") (pintype "bidirectional"))
      (node (ref "J8") (pin "2") (pinfunction "2_2") (pintype "bidirectional"))
      (node (ref "J9") (pin "2") (pinfunction "2_2") (pintype "bidirectional"))
      (node (ref "L7") (pin "1") (pinfunction "1_1") (pintype "passive"))
      (node (ref "L8") (pin "1") (pinfunction "1_1") (pintype "passive"))
      (node (ref "Q1") (pin "2") (pinfunction "S_2") (pintype "passive"))
      (node (ref "Q2") (pin "2") (pinfunction "S_2") (pintype "passive"))
      (node (ref "R12") (pin "1") (pinfunction "1_1") (pintype "passive"))
      (node (ref "R13") (pin "1") (pinfunction "1_1") (pintype "passive"))
      (node (ref "R14") (pin "1") (pinfunction "1_1") (pintype "passive"))
      (node (ref "R22") (pin "1") (pinfunction "1_1") (pintype "passive"))
      (node (ref "R24") (pin "1") (pinfunction "1_1") (pintype "passive"))
      (node (ref "R26") (pin "1") (pinfunction "1_1") (pintype "passive"))
      (node (ref "R27") (pin "1") (pinfunction "1_1") (pintype "passive"))
      (node (ref "R31") (pin "1") (pinfunction "1_1") (pintype "passive"))
      (node (ref "R34") (pin "1") (pinfunction "1_1") (pintype "passive"))
      (node (ref "R37") (pin "1") (pinfunction "1_1") (pintype "passive"))
      (node (ref "R41") (pin "1") (pinfunction "1_1") (pintype "passive"))
      (node (ref "U2") (pin "P$10") (pinfunction "RES_P$10") (pintype "bidirectional"))
      (node (ref "U2") (pin "P$12") (pinfunction "GND_P$12") (pintype "power_in"))
      (node (ref "U2") (pin "P$13") (pinfunction "GND_P$13") (pintype "power_in"))
      (node (ref "U2") (pin "P$16") (pinfunction "GND_P$16") (pintype "power_in"))
      (node (ref "U2") (pin "P$5") (pinfunction "GND_P$5") (pintype "power_in"))
      (node (ref "U5") (pin "9") (pinfunction "GND_9") (pintype "bidirectional"))
      (node (ref "U6") (pin "9") (pinfunction "GND_9") (pintype "bidirectional"))
      (node (ref "X1") (pin "5") (pinfunction "S_5") (pintype "passive"))
    )
    (net (code "55") (name "Net-(BAT46WH1-A)") (class "Default")
      (node (ref "BAT46WH1") (pin "2") (pinfunction "A_2") (pintype "passive"))
      (node (ref "L2") (pin "2") (pinfunction "2_2") (pintype "passive"))
      (node (ref "Q1") (pin "3") (pinfunction "D_3") (pintype "passive"))
    )
    (net (code "56") (name "Net-(BAT46WH1-K)") (class "Default")
      (node (ref "BAT46WH1") (pin "1") (pinfunction "K_1") (pintype "passive"))
      (node (ref "C23") (pin "1") (pinfunction "1_1") (pintype "passive"))
      (node (ref "R20") (pin "2") (pinfunction "2_2") (pintype "passive"))
      (node (ref "U5") (pin "4") (pinfunction "CS+_4") (pintype "bidirectional"))
    )
    (net (code "57") (name "Net-(BAT46WH2-A)") (class "Default")
      (node (ref "BAT46WH2") (pin "2") (pinfunction "A_2") (pintype "passive"))
      (node (ref "L9") (pin "2") (pinfunction "2_2") (pintype "passive"))
      (node (ref "Q2") (pin "3") (pinfunction "D_3") (pintype "passive"))
    )
    (net (code "58") (name "Net-(BAT46WH2-K)") (class "Default")
      (node (ref "BAT46WH2") (pin "1") (pinfunction "K_1") (pintype "passive"))
      (node (ref "C29") (pin "1") (pinfunction "1_1") (pintype "passive"))
      (node (ref "R28") (pin "2") (pinfunction "2_2") (pintype "passive"))
      (node (ref "U6") (pin "4") (pinfunction "CS+_4") (pintype "bidirectional"))
    )
    (net (code "59") (name "Net-(C22-Pad1)") (class "Default")
      (node (ref "C22") (pin "1") (pinfunction "1_1") (pintype "passive"))
      (node (ref "R18") (pin "2") (pinfunction "2_2") (pintype "passive"))
    )
    (net (code "60") (name "Net-(C30-Pad1)") (class "Default")
      (node (ref "C30") (pin "1") (pinfunction "1_1") (pintype "passive"))
      (node (ref "R32") (pin "2") (pinfunction "2_2") (pintype "passive"))
    )
    (net (code "61") (name "Net-(D1-Pad1)") (class "Default")
      (node (ref "D1") (pin "1") (pinfunction "1_1") (pintype "passive"))
      (node (ref "R16") (pin "2") (pinfunction "2_2") (pintype "passive"))
    )
    (net (code "62") (name "Net-(D1-Pad3)") (class "Default")
      (node (ref "D1") (pin "3") (pinfunction "3_3") (pintype "passive"))
      (node (ref "R17") (pin "2") (pinfunction "2_2") (pintype "passive"))
    )
    (net (code "63") (name "Net-(IC$3-OUTA)") (class "Default")
      (node (ref "IC$3") (pin "1") (pinfunction "OUTA_1") (pintype "output"))
      (node (ref "R7") (pin "1") (pinfunction "1_1") (pintype "passive"))
    )
    (net (code "64") (name "Net-(IC$3-OUTB)") (class "Default")
      (node (ref "IC$3") (pin "7") (pinfunction "OUTB_7") (pintype "output"))
      (node (ref "R8") (pin "1") (pinfunction "1_1") (pintype "passive"))
    )
    (net (code "65") (name "Net-(IC1A-O)") (class "Default")
      (node (ref "IC1") (pin "4") (pinfunction "O_4") (pintype "output"))
      (node (ref "IC2") (pin "2") (pinfunction "TR_2") (pintype "input"))
      (node (ref "R9") (pin "1") (pinfunction "1_1") (pintype "passive"))
    )
    (net (code "66") (name "Net-(IC2-CV)") (class "Default")
      (node (ref "C17") (pin "2") (pinfunction "2_2") (pintype "passive"))
      (node (ref "IC2") (pin "5") (pinfunction "CV_5") (pintype "input"))
    )
    (net (code "67") (name "Net-(IC2-DIS)") (class "Default")
      (node (ref "C19") (pin "2") (pinfunction "2_2") (pintype "passive"))
      (node (ref "IC2") (pin "6") (pinfunction "THR_6") (pintype "input"))
      (node (ref "IC2") (pin "7") (pinfunction "DIS_7") (pintype "input"))
      (node (ref "R10") (pin "1") (pinfunction "1_1") (pintype "passive"))
    )
    (net (code "68") (name "Net-(IC3-CV)") (class "Default")
      (node (ref "C36") (pin "2") (pinfunction "2_2") (pintype "passive"))
      (node (ref "IC3") (pin "5") (pinfunction "CV_5") (pintype "input"))
    )
    (net (code "69") (name "Net-(IC3-DIS)") (class "Default")
      (node (ref "C37") (pin "2") (pinfunction "2_2") (pintype "passive"))
      (node (ref "IC3") (pin "6") (pinfunction "THR_6") (pintype "input"))
      (node (ref "IC3") (pin "7") (pinfunction "DIS_7") (pintype "input"))
      (node (ref "R36") (pin "1") (pinfunction "1_1") (pintype "passive"))
    )
    (net (code "70") (name "Net-(IC3-TR)") (class "Default")
      (node (ref "IC3") (pin "2") (pinfunction "TR_2") (pintype "input"))
      (node (ref "IC5") (pin "4") (pinfunction "O_4") (pintype "output"))
      (node (ref "R35") (pin "1") (pinfunction "1_1") (pintype "passive"))
    )
    (net (code "71") (name "Net-(IC4-CV)") (class "Default")
      (node (ref "C39") (pin "2") (pinfunction "2_2") (pintype "passive"))
      (node (ref "IC4") (pin "5") (pinfunction "CV_5") (pintype "input"))
    )
    (net (code "72") (name "Net-(IC4-DIS)") (class "Default")
      (node (ref "C40") (pin "2") (pinfunction "2_2") (pintype "passive"))
      (node (ref "IC4") (pin "6") (pinfunction "THR_6") (pintype "input"))
      (node (ref "IC4") (pin "7") (pinfunction "DIS_7") (pintype "input"))
      (node (ref "R40") (pin "1") (pinfunction "1_1") (pintype "passive"))
    )
    (net (code "73") (name "Net-(IC4-TR)") (class "Default")
      (node (ref "IC4") (pin "2") (pinfunction "TR_2") (pintype "input"))
      (node (ref "IC6") (pin "4") (pinfunction "O_4") (pintype "output"))
      (node (ref "R39") (pin "1") (pinfunction "1_1") (pintype "passive"))
    )
    (net (code "74") (name "Net-(J5-SIG)") (class "Default")
      (node (ref "C1") (pin "1") (pinfunction "1_1") (pintype "passive"))
      (node (ref "J5") (pin "5") (pinfunction "SIG_5") (pintype "passive"))
      (node (ref "L1") (pin "1") (pinfunction "1_1") (pintype "passive"))
      (node (ref "R1") (pin "1") (pinfunction "1_1") (pintype "passive"))
    )
    (net (code "75") (name "Net-(L1-Pad2)") (class "Default")
      (node (ref "L1") (pin "2") (pinfunction "2_2") (pintype "passive"))
      (node (ref "R2") (pin "2") (pinfunction "2_2") (pintype "passive"))
    )
    (net (code "76") (name "Net-(Q1-G)") (class "Default")
      (node (ref "Q1") (pin "1") (pinfunction "G_1") (pintype "passive"))
      (node (ref "U5") (pin "10") (pinfunction "GATE_10") (pintype "bidirectional"))
    )
    (net (code "77") (name "Net-(Q2-G)") (class "Default")
      (node (ref "Q2") (pin "1") (pinfunction "G_1") (pintype "passive"))
      (node (ref "U6") (pin "10") (pinfunction "GATE_10") (pintype "bidirectional"))
    )
    (net (code "78") (name "Net-(U1-RF_IN)") (class "Default")
      (node (ref "C2") (pin "1") (pinfunction "1_1") (pintype "passive"))
      (node (ref "R1") (pin "2") (pinfunction "2_2") (pintype "passive"))
      (node (ref "U1") (pin "11") (pinfunction "RF_IN_11") (pintype "bidirectional"))
    )
    (net (code "79") (name "Net-(U1-VCC_RF)") (class "Default")
      (node (ref "R2") (pin "1") (pinfunction "1_1") (pintype "passive"))
      (node (ref "U1") (pin "14") (pinfunction "VCC_RF_14") (pintype "output"))
    )
    (net (code "80") (name "Net-(U2-C1)") (class "Default")
      (node (ref "C8") (pin "1") (pinfunction "1_1") (pintype "passive"))
      (node (ref "U2") (pin "P$15") (pinfunction "C1_P$15") (pintype "bidirectional"))
    )
    (net (code "81") (name "Net-(U2-SETC)") (class "Default")
      (node (ref "C9") (pin "2") (pinfunction "2_2") (pintype "passive"))
      (node (ref "U2") (pin "P$2") (pinfunction "SETC_P$2") (pintype "bidirectional"))
    )
    (net (code "82") (name "Net-(U2-SETP)") (class "Default")
      (node (ref "C9") (pin "1") (pinfunction "1_1") (pintype "passive"))
      (node (ref "U2") (pin "P$3") (pinfunction "SETP_P$3") (pintype "bidirectional"))
    )
    (net (code "83") (name "Net-(U5-COMP)") (class "Default")
      (node (ref "R18") (pin "1") (pinfunction "1_1") (pintype "passive"))
      (node (ref "U5") (pin "8") (pinfunction "COMP_8") (pintype "bidirectional"))
    )
    (net (code "84") (name "Net-(U5-DACOUT)") (class "Default")
      (node (ref "R19") (pin "1") (pinfunction "1_1") (pintype "passive"))
      (node (ref "U5") (pin "6") (pinfunction "DACOUT_6") (pintype "bidirectional"))
    )
    (net (code "85") (name "Net-(U5-FB)") (class "Default")
      (node (ref "R19") (pin "2") (pinfunction "2_2") (pintype "passive"))
      (node (ref "R21") (pin "1") (pinfunction "1_1") (pintype "passive"))
      (node (ref "R22") (pin "2") (pinfunction "2_2") (pintype "passive"))
      (node (ref "U5") (pin "7") (pinfunction "FB_7") (pintype "bidirectional"))
    )
    (net (code "86") (name "Net-(U6-COMP)") (class "Default")
      (node (ref "R32") (pin "1") (pinfunction "1_1") (pintype "passive"))
      (node (ref "U6") (pin "8") (pinfunction "COMP_8") (pintype "bidirectional"))
    )
    (net (code "87") (name "Net-(U6-DACOUT)") (class "Default")
      (node (ref "R29") (pin "1") (pinfunction "1_1") (pintype "passive"))
      (node (ref "U6") (pin "6") (pinfunction "DACOUT_6") (pintype "bidirectional"))
    )
    (net (code "88") (name "Net-(U6-FB)") (class "Default")
      (node (ref "R29") (pin "2") (pinfunction "2_2") (pintype "passive"))
      (node (ref "R30") (pin "1") (pinfunction "1_1") (pintype "passive"))
      (node (ref "R31") (pin "2") (pinfunction "2_2") (pintype "passive"))
      (node (ref "U6") (pin "7") (pinfunction "FB_7") (pintype "bidirectional"))
    )
    (net (code "89") (name "unconnected-(DUE1-Pad5V_A)") (class "Default")
      (node (ref "DUE1") (pin "5V_A") (pinfunction "5V_A_5V_A") (pintype "bidirectional"))
    )
    (net (code "90") (name "unconnected-(DUE1-Pad5V_B)") (class "Default")
      (node (ref "DUE1") (pin "5V_B") (pinfunction "5V_B_5V_B") (pintype "bidirectional"))
    )
    (net (code "91") (name "unconnected-(DUE1-Pad22)") (class "Default")
      (node (ref "DUE1") (pin "22") (pinfunction "22_22") (pintype "bidirectional"))
    )
    (net (code "92") (name "unconnected-(DUE1-Pad23)") (class "Default")
      (node (ref "DUE1") (pin "23") (pinfunction "23_23") (pintype "bidirectional"))
    )
    (net (code "93") (name "unconnected-(DUE1-Pad24)") (class "Default")
      (node (ref "DUE1") (pin "24") (pinfunction "24_24") (pintype "bidirectional"))
    )
    (net (code "94") (name "unconnected-(DUE1-Pad25)") (class "Default")
      (node (ref "DUE1") (pin "25") (pinfunction "25_25") (pintype "bidirectional"))
    )
    (net (code "95") (name "unconnected-(DUE1-Pad26)") (class "Default")
      (node (ref "DUE1") (pin "26") (pinfunction "26_26") (pintype "bidirectional"))
    )
    (net (code "96") (name "unconnected-(DUE1-Pad27)") (class "Default")
      (node (ref "DUE1") (pin "27") (pinfunction "27_27") (pintype "bidirectional"))
    )
    (net (code "97") (name "unconnected-(DUE1-Pad28)") (class "Default")
      (node (ref "DUE1") (pin "28") (pinfunction "28_28") (pintype "bidirectional"))
    )
    (net (code "98") (name "unconnected-(DUE1-Pad29)") (class "Default")
      (node (ref "DUE1") (pin "29") (pinfunction "29_29") (pintype "bidirectional"))
    )
    (net (code "99") (name "unconnected-(DUE1-Pad30)") (class "Default")
      (node (ref "DUE1") (pin "30") (pinfunction "30_30") (pintype "bidirectional"))
    )
    (net (code "100") (name "unconnected-(DUE1-Pad31)") (class "Default")
      (node (ref "DUE1") (pin "31") (pinfunction "31_31") (pintype "bidirectional"))
    )
    (net (code "101") (name "unconnected-(DUE1-Pad32)") (class "Default")
      (node (ref "DUE1") (pin "32") (pinfunction "32_32") (pintype "bidirectional"))
    )
    (net (code "102") (name "unconnected-(DUE1-Pad33)") (class "Default")
      (node (ref "DUE1") (pin "33") (pinfunction "33_33") (pintype "bidirectional"))
    )
    (net (code "103") (name "unconnected-(DUE1-Pad34)") (class "Default")
      (node (ref "DUE1") (pin "34") (pinfunction "34_34") (pintype "bidirectional"))
    )
    (net (code "104") (name "unconnected-(DUE1-Pad35)") (class "Default")
      (node (ref "DUE1") (pin "35") (pinfunction "35_35") (pintype "bidirectional"))
    )
    (net (code "105") (name "unconnected-(DUE1-Pad36)") (class "Default")
      (node (ref "DUE1") (pin "36") (pinfunction "36_36") (pintype "bidirectional"))
    )
    (net (code "106") (name "unconnected-(DUE1-Pad37)") (class "Default")
      (node (ref "DUE1") (pin "37") (pinfunction "37_37") (pintype "bidirectional"))
    )
    (net (code "107") (name "unconnected-(DUE1-Pad38)") (class "Default")
      (node (ref "DUE1") (pin "38") (pinfunction "38_38") (pintype "bidirectional"))
    )
    (net (code "108") (name "unconnected-(DUE1-Pad39)") (class "Default")
      (node (ref "DUE1") (pin "39") (pinfunction "39_39") (pintype "bidirectional"))
    )
    (net (code "109") (name "unconnected-(DUE1-Pad40)") (class "Default")
      (node (ref "DUE1") (pin "40") (pinfunction "40_40") (pintype "bidirectional"))
    )
    (net (code "110") (name "unconnected-(DUE1-Pad41)") (class "Default")
      (node (ref "DUE1") (pin "41") (pinfunction "41_41") (pintype "bidirectional"))
    )
    (net (code "111") (name "unconnected-(DUE1-Pad42)") (class "Default")
      (node (ref "DUE1") (pin "42") (pinfunction "42_42") (pintype "bidirectional"))
    )
    (net (code "112") (name "unconnected-(DUE1-Pad43)") (class "Default")
      (node (ref "DUE1") (pin "43") (pinfunction "43_43") (pintype "bidirectional"))
    )
    (net (code "113") (name "unconnected-(DUE1-Pad44)") (class "Default")
      (node (ref "DUE1") (pin "44") (pinfunction "44_44") (pintype "bidirectional"))
    )
    (net (code "114") (name "unconnected-(DUE1-Pad45)") (class "Default")
      (node (ref "DUE1") (pin "45") (pinfunction "45_45") (pintype "bidirectional"))
    )
    (net (code "115") (name "unconnected-(DUE1-Pad46)") (class "Default")
      (node (ref "DUE1") (pin "46") (pinfunction "46_46") (pintype "bidirectional"))
    )
    (net (code "116") (name "unconnected-(DUE1-Pad47)") (class "Default")
      (node (ref "DUE1") (pin "47") (pinfunction "47_47") (pintype "bidirectional"))
    )
    (net (code "117") (name "unconnected-(DUE1-Pad48)") (class "Default")
      (node (ref "DUE1") (pin "48") (pinfunction "48_48") (pintype "bidirectional"))
    )
    (net (code "118") (name "unconnected-(DUE1-Pad49)") (class "Default")
      (node (ref "DUE1") (pin "49") (pinfunction "49_49") (pintype "bidirectional"))
    )
    (net (code "119") (name "unconnected-(DUE1-Pad50)") (class "Default")
      (node (ref "DUE1") (pin "50") (pinfunction "50_50") (pintype "bidirectional"))
    )
    (net (code "120") (name "unconnected-(DUE1-Pad51)") (class "Default")
      (node (ref "DUE1") (pin "51") (pinfunction "51_51") (pintype "bidirectional"))
    )
    (net (code "121") (name "unconnected-(DUE1-Pad52)") (class "Default")
      (node (ref "DUE1") (pin "52") (pinfunction "52_52") (pintype "bidirectional"))
    )
    (net (code "122") (name "unconnected-(DUE1-Pad53)") (class "Default")
      (node (ref "DUE1") (pin "53") (pinfunction "53_53") (pintype "bidirectional"))
    )
    (net (code "123") (name "unconnected-(DUE1-PadAREF)") (class "Default")
      (node (ref "DUE1") (pin "AREF") (pinfunction "AREF_AREF") (pintype "bidirectional"))
    )
    (net (code "124") (name "unconnected-(DUE1-PadCANRX)") (class "Default")
      (node (ref "DUE1") (pin "CANRX") (pinfunction "CANRX_CANRX") (pintype "bidirectional"))
    )
    (net (code "125") (name "unconnected-(DUE1-PadCANTX)") (class "Default")
      (node (ref "DUE1") (pin "CANTX") (pinfunction "CANTX_CANTX") (pintype "bidirectional"))
    )
    (net (code "126") (name "unconnected-(DUE1-PadIOREF)") (class "Default")
      (node (ref "DUE1") (pin "IOREF") (pinfunction "IOREF_IOREF") (pintype "bidirectional"))
    )
    (net (code "127") (name "unconnected-(DUE1-PadNC)") (class "Default")
      (node (ref "DUE1") (pin "NC") (pinfunction "NC_NC") (pintype "bidirectional"))
    )
    (net (code "128") (name "unconnected-(DUE1-PadSCL1)") (class "Default")
      (node (ref "DUE1") (pin "SCL1") (pinfunction "SCL1_SCL1") (pintype "bidirectional"))
    )
    (net (code "129") (name "unconnected-(DUE1-PadVIN)") (class "Default")
      (node (ref "DUE1") (pin "VIN") (pinfunction "VIN_VIN") (pintype "bidirectional"))
    )
    (net (code "130") (name "unconnected-(J5-GND-Pad2)") (class "Default")
      (node (ref "J5") (pin "2") (pinfunction "GND_2") (pintype "passive"))
    )
    (net (code "131") (name "unconnected-(J5-GND-Pad3)") (class "Default")
      (node (ref "J5") (pin "3") (pinfunction "GND_3") (pintype "passive"))
    )
    (net (code "132") (name "unconnected-(J5-GND-Pad4)") (class "Default")
      (node (ref "J5") (pin "4") (pinfunction "GND_4") (pintype "passive"))
    )
    (net (code "133") (name "unconnected-(U1-ANTON-Pad13)") (class "Default")
      (node (ref "U1") (pin "13") (pinfunction "ANTON_13") (pintype "output"))
    )
    (net (code "134") (name "unconnected-(U1-FORCE_ON-Pad18)") (class "Default")
      (node (ref "U1") (pin "18") (pinfunction "FORCE_ON_18") (pintype "bidirectional"))
    )
    (net (code "135") (name "unconnected-(U1-RESERVED-Pad16)") (class "Default")
      (node (ref "U1") (pin "16") (pinfunction "RESERVED_16") (pintype "passive"))
    )
    (net (code "136") (name "unconnected-(U1-RESERVED-Pad17)") (class "Default")
      (node (ref "U1") (pin "17") (pinfunction "RESERVED_17") (pintype "passive"))
    )
    (net (code "137") (name "unconnected-(U1-STANDBY-Pad5)") (class "Default")
      (node (ref "U1") (pin "5") (pinfunction "STANDBY_5") (pintype "bidirectional"))
    )
  )
)
